# Digital.net
KiCad netlist of a schematic drawn in Altium Designer
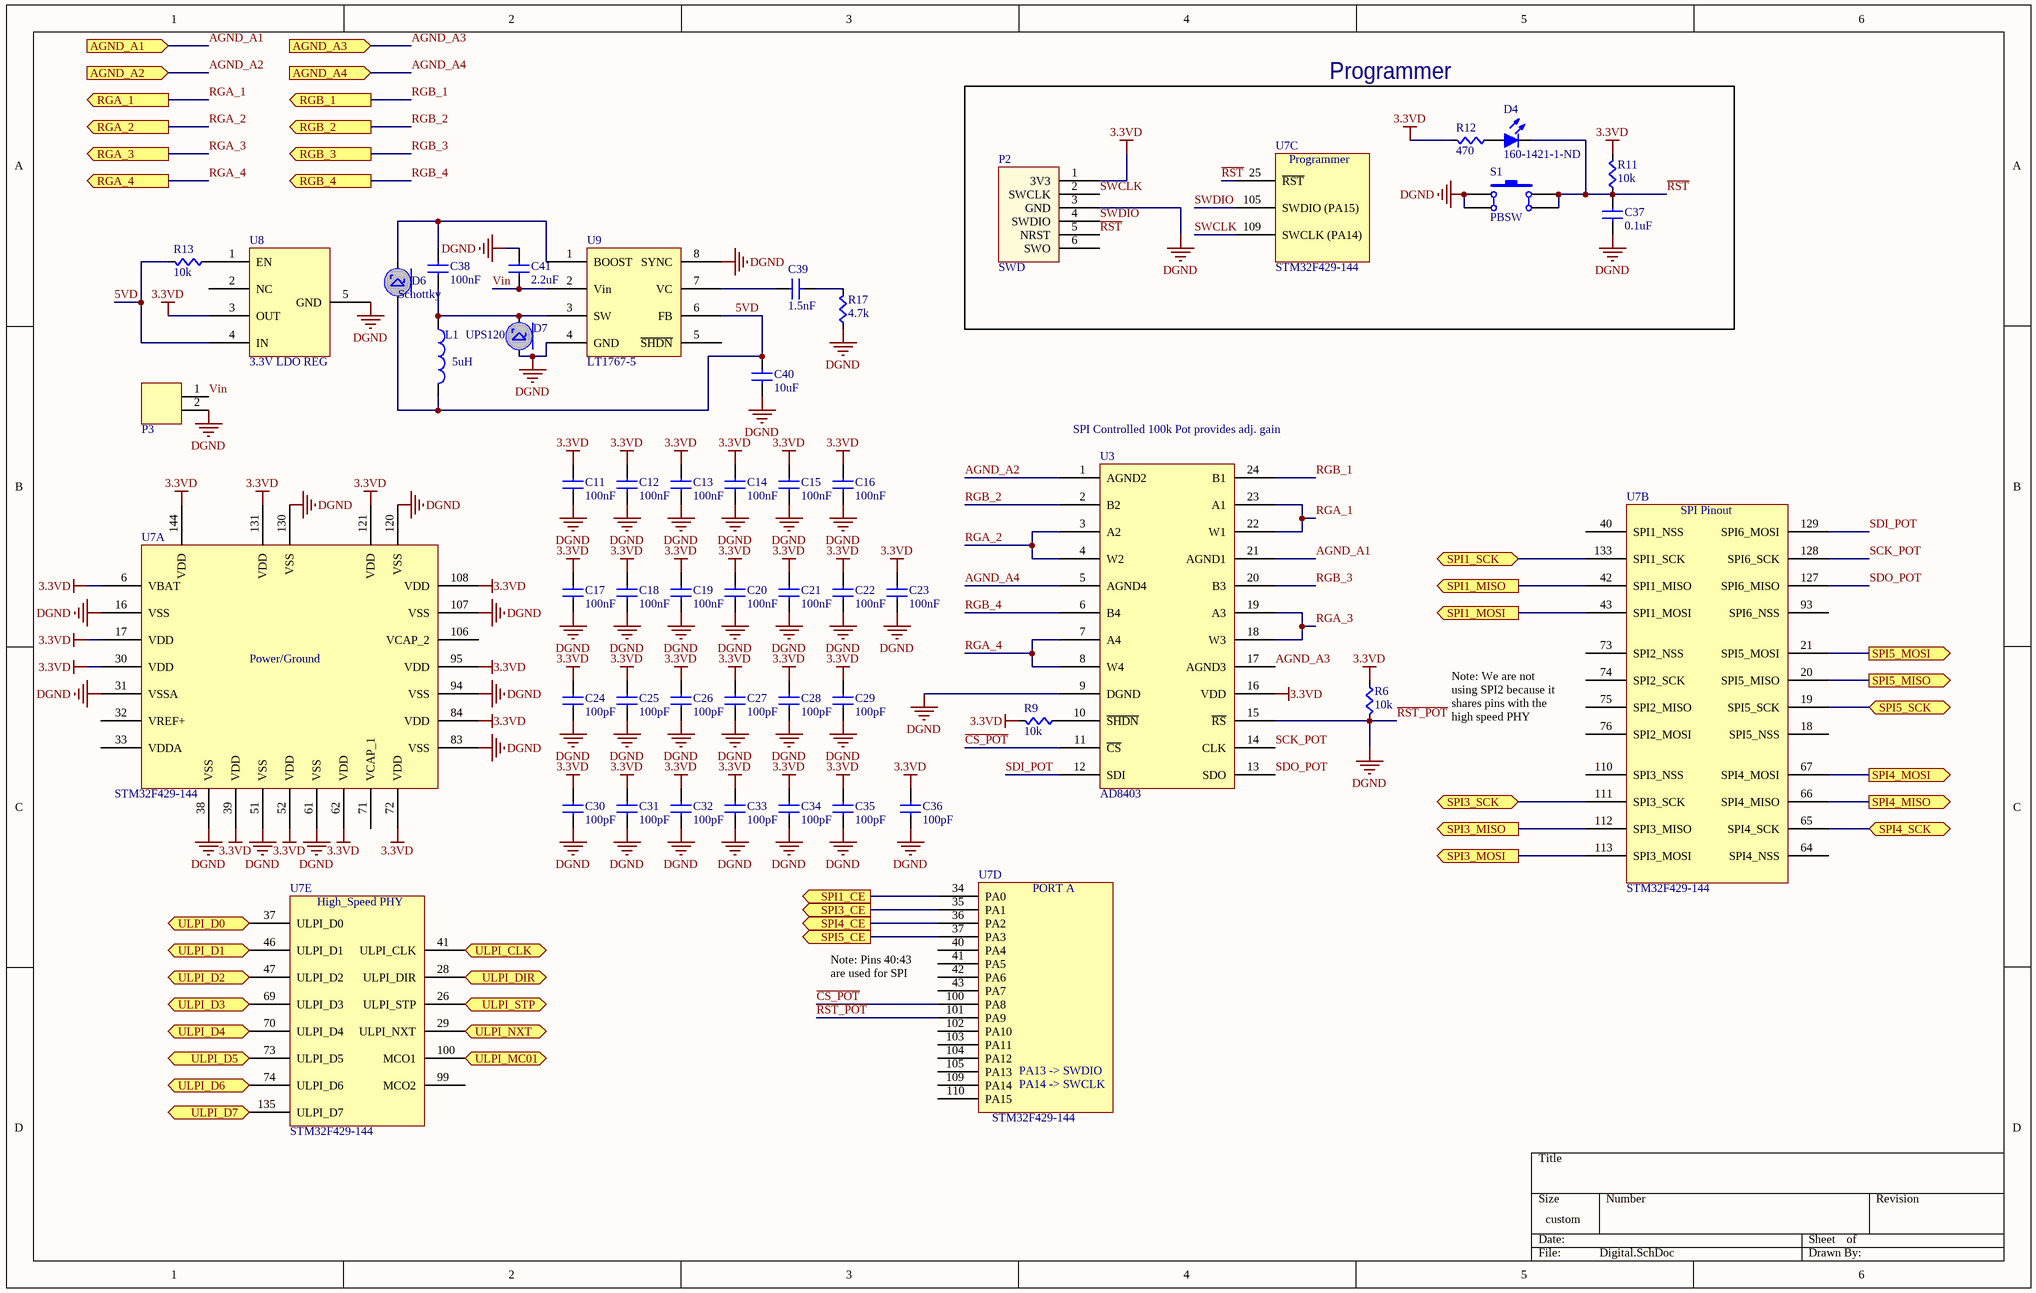
[diagram p0: Digital.SchDoc]

(export (version "E")
  (design (tool "Eeschema 10.0.6"))
  (components
    (comp (ref "C11")
      (value "100nF")
      (footprint "CAPC0603")
      (fields (field (name "Comment") "Cap"))
      (libsource (lib "SubjuGator8") (part "Cap"))
    )
    (comp (ref "C12")
      (value "100nF")
      (footprint "CAPC0603")
      (fields (field (name "Comment") "Cap"))
      (libsource (lib "SubjuGator8") (part "Cap"))
    )
    (comp (ref "C13")
      (value "100nF")
      (footprint "CAPC0603")
      (fields (field (name "Comment") "Cap"))
      (libsource (lib "SubjuGator8") (part "Cap"))
    )
    (comp (ref "C14")
      (value "100nF")
      (footprint "CAPC0603")
      (fields (field (name "Comment") "Cap"))
      (libsource (lib "SubjuGator8") (part "Cap"))
    )
    (comp (ref "C15")
      (value "100nF")
      (footprint "CAPC0603")
      (fields (field (name "Comment") "Cap"))
      (libsource (lib "SubjuGator8") (part "Cap"))
    )
    (comp (ref "C16")
      (value "100nF")
      (footprint "CAPC0603")
      (fields (field (name "Comment") "Cap"))
      (libsource (lib "SubjuGator8") (part "Cap"))
    )
    (comp (ref "C17")
      (value "100nF")
      (footprint "CAPC0603")
      (fields (field (name "Comment") "Cap"))
      (libsource (lib "SubjuGator8") (part "Cap"))
    )
    (comp (ref "C18")
      (value "100nF")
      (footprint "CAPC0603")
      (fields (field (name "Comment") "Cap"))
      (libsource (lib "SubjuGator8") (part "Cap"))
    )
    (comp (ref "C19")
      (value "100nF")
      (footprint "CAPC0603")
      (fields (field (name "Comment") "Cap"))
      (libsource (lib "SubjuGator8") (part "Cap"))
    )
    (comp (ref "C20")
      (value "100nF")
      (footprint "CAPC0603")
      (fields (field (name "Comment") "Cap"))
      (libsource (lib "SubjuGator8") (part "Cap"))
    )
    (comp (ref "C21")
      (value "100nF")
      (footprint "CAPC0603")
      (fields (field (name "Comment") "Cap"))
      (libsource (lib "SubjuGator8") (part "Cap"))
    )
    (comp (ref "C22")
      (value "100nF")
      (footprint "CAPC0603")
      (fields (field (name "Comment") "Cap"))
      (libsource (lib "SubjuGator8") (part "Cap"))
    )
    (comp (ref "C23")
      (value "100nF")
      (footprint "CAPC0603")
      (fields (field (name "Comment") "Cap"))
      (libsource (lib "SubjuGator8") (part "Cap"))
    )
    (comp (ref "C24")
      (value "100pF")
      (footprint "CAPC0603")
      (fields (field (name "Comment") "Cap"))
      (libsource (lib "SubjuGator8") (part "Cap"))
    )
    (comp (ref "C25")
      (value "100pF")
      (footprint "CAPC0603")
      (fields (field (name "Comment") "Cap"))
      (libsource (lib "SubjuGator8") (part "Cap"))
    )
    (comp (ref "C26")
      (value "100pF")
      (footprint "CAPC0603")
      (fields (field (name "Comment") "Cap"))
      (libsource (lib "SubjuGator8") (part "Cap"))
    )
    (comp (ref "C27")
      (value "100pF")
      (footprint "CAPC0603")
      (fields (field (name "Comment") "Cap"))
      (libsource (lib "SubjuGator8") (part "Cap"))
    )
    (comp (ref "C28")
      (value "100pF")
      (footprint "CAPC0603")
      (fields (field (name "Comment") "Cap"))
      (libsource (lib "SubjuGator8") (part "Cap"))
    )
    (comp (ref "C29")
      (value "100pF")
      (footprint "CAPC0603")
      (fields (field (name "Comment") "Cap"))
      (libsource (lib "SubjuGator8") (part "Cap"))
    )
    (comp (ref "C30")
      (value "100pF")
      (footprint "CAPC0603")
      (fields (field (name "Comment") "Cap"))
      (libsource (lib "SubjuGator8") (part "Cap"))
    )
    (comp (ref "C31")
      (value "100pF")
      (footprint "CAPC0603")
      (fields (field (name "Comment") "Cap"))
      (libsource (lib "SubjuGator8") (part "Cap"))
    )
    (comp (ref "C32")
      (value "100pF")
      (footprint "CAPC0603")
      (fields (field (name "Comment") "Cap"))
      (libsource (lib "SubjuGator8") (part "Cap"))
    )
    (comp (ref "C33")
      (value "100pF")
      (footprint "CAPC0603")
      (fields (field (name "Comment") "Cap"))
      (libsource (lib "SubjuGator8") (part "Cap"))
    )
    (comp (ref "C34")
      (value "100pF")
      (footprint "CAPC0603")
      (fields (field (name "Comment") "Cap"))
      (libsource (lib "SubjuGator8") (part "Cap"))
    )
    (comp (ref "C35")
      (value "100pF")
      (footprint "CAPC0603")
      (fields (field (name "Comment") "Cap"))
      (libsource (lib "SubjuGator8") (part "Cap"))
    )
    (comp (ref "C36")
      (value "100pF")
      (footprint "CAPC0603")
      (fields (field (name "Comment") "Cap"))
      (libsource (lib "SubjuGator8") (part "Cap"))
    )
    (comp (ref "C37")
      (value "0.1uF")
      (footprint "CAPC0603")
      (fields (field (name "Comment") "Cap"))
      (libsource (lib "SubjuGator8") (part "Cap"))
    )
    (comp (ref "C38")
      (value "100nF")
      (footprint "CAPC0603")
      (fields (field (name "Comment") "Cap"))
      (libsource (lib "SubjuGator8") (part "Cap"))
    )
    (comp (ref "C39")
      (value "1.5nF")
      (footprint "CAPC0603")
      (fields (field (name "Comment") "Cap"))
      (libsource (lib "SubjuGator8") (part "Cap"))
    )
    (comp (ref "C40")
      (value "10uF")
      (footprint "CAPC0603")
      (fields (field (name "Comment") "Cap"))
      (libsource (lib "SubjuGator8") (part "Cap"))
    )
    (comp (ref "C41")
      (value "2.2uF")
      (footprint "CAPC0603")
      (fields (field (name "Comment") "Cap"))
      (libsource (lib "SubjuGator8") (part "Cap"))
    )
    (comp (ref "D4")
      (value "LED-RED")
      (footprint "Hydrophone:LED0805-RED")
      (description "Light Emitting Diode - RED")
      (fields
        (field (name "MANUFACTURER PART NUMBER") "LTST-C171CKT")
        (field (name "MANUFACTURER") "Lite-On Inc")
        (field (name "SUPPLIER PART NUMBER") "160-1421-1-ND")
      )
      (libsource (lib "Hydrophone") (part "LED-RED"))
    )
    (comp (ref "D6")
      (value "Schottky")
      (footprint "SOD-323F")
      (description "DIODE SCHOTTKY 30V 100MA SOD323")
      (libsource (lib "Semiconductors") (part "CMDSH-3"))
    )
    (comp (ref "D7")
      (value "UPS120")
      (footprint "DO-216AA")
      (description "DIODE SCHOTTKY 20V 1A POWERMITE1")
      (libsource (lib "SubjuGator8") (part "UPS120"))
    )
    (comp (ref "L1")
      (value "5uH")
      (footprint "IND_2")
      (description "FIXED IND 5UH 4.7A 22 MOHM SMD")
      (libsource (lib "Passives") (part "SRR1206-5R0ML"))
    )
    (comp (ref "P2")
      (value "SWD")
      (footprint "SWD_STM32")
      (description "SWD connector matching the pinout on STM Discovery Boards")
      (libsource (lib "SubjuGator8") (part "SWD_STM32"))
    )
    (comp (ref "P3")
      (value "2-pin Horz Sherlock")
      (footprint "MOLEX-HDR-1X2-SHERLOCK-HORZ")
      (fields
        (field (name "MANUFACTURER PART NUMBER") "0353630260")
        (field (name "MANUFACTURER") "Molex Inc")
      )
      (libsource (lib "SubjuGator8") (part "MOLEX-HDR-1x2-SHERLOCK_RA"))
    )
    (comp (ref "R6")
      (value "10k")
      (footprint "RES0603")
      (fields (field (name "Comment") "Res"))
      (libsource (lib "SubjuGator8") (part "Res"))
    )
    (comp (ref "R9")
      (value "10k")
      (footprint "RES0603")
      (fields (field (name "Comment") "Res"))
      (libsource (lib "SubjuGator8") (part "Res"))
    )
    (comp (ref "R11")
      (value "10k")
      (footprint "RES0603")
      (fields (field (name "Comment") "Res"))
      (libsource (lib "Passives") (part "Res"))
    )
    (comp (ref "R12")
      (value "470")
      (footprint "RES0603")
      (fields (field (name "Comment") "Res"))
      (libsource (lib "SubjuGator8") (part "Res"))
    )
    (comp (ref "R13")
      (value "10k")
      (footprint "RES0603")
      (fields (field (name "Comment") "Res"))
      (libsource (lib "SubjuGator8") (part "Res"))
    )
    (comp (ref "R17")
      (value "4.7k")
      (footprint "RES0603")
      (fields (field (name "Comment") "Res"))
      (libsource (lib "SubjuGator8") (part "Res"))
    )
    (comp (ref "S1")
      (value "PBSW")
      (footprint "Hydrophone:PBSW")
      (description "Push Button Switch")
      (fields
        (field (name "MANUFACTURER") "Panasonic Electronic Components")
        (field (name "MANUFACTURER PART NUMBER") "EVQ-9P105M")
        (field (name "PUBLISHER") "Altium Limited")
      )
      (libsource (lib "Hydrophone") (part "SW-PB"))
    )
    (comp (ref "U3")
      (value "AD8403")
      (footprint "SOIC-24n")
      (description "IC POT DGTL 8BIT 100K 4CH 24SOIC")
      (libsource (lib "SubjuGator8") (part "AD8403"))
    )
    (comp (ref "U7")
      (value "STM32F429-144")
      (footprint "LQFP-144")
      (description "IC MCU ARM 2MB FLASH 144LQFP")
      (libsource (lib "SubjuGator8") (part "STM32F429-144"))
    )
    (comp (ref "U8")
      (value "3.3V LDO REG")
      (footprint "SOT223-8N")
      (description "IC REG LDO 3.3V 0.5A SOT223-5")
      (libsource (lib "SubjuGator8") (part "LP38691"))
    )
    (comp (ref "U9")
      (value "LT1767-5")
      (footprint "MSOP-8n")
      (description "IC REG BUCK 5V 1.5A 8MSOP")
      (libsource (lib "SubjuGator8") (part "LT1767-5"))
    )
  )
  (nets
    (net (code "1") (name "/5VD") (class "Default")
      (node (ref "C40") (pin "1") (pinfunction "A_1") (pintype "passive"))
      (node (ref "D6") (pin "A") (pinfunction "A_A") (pintype "passive"))
      (node (ref "L1") (pin "2") (pinfunction "B_2") (pintype "passive"))
      (node (ref "R13") (pin "1") (pinfunction "A_1") (pintype "passive"))
      (node (ref "U8") (pin "4") (pinfunction "IN_4") (pintype "passive"))
      (node (ref "U9") (pin "6") (pinfunction "FB_6") (pintype "passive"))
    )
    (net (code "2") (name "/AGND_A1") (class "Default")
      (node (ref "U3") (pin "21") (pinfunction "AGND1_21") (pintype "passive"))
    )
    (net (code "3") (name "/AGND_A2") (class "Default")
      (node (ref "U3") (pin "1") (pinfunction "AGND2_1") (pintype "passive"))
    )
    (net (code "4") (name "/AGND_A3") (class "Default")
      (node (ref "U3") (pin "17") (pinfunction "AGND3_17") (pintype "passive"))
    )
    (net (code "5") (name "/AGND_A4") (class "Default")
      (node (ref "U3") (pin "5") (pinfunction "AGND4_5") (pintype "passive"))
    )
    (net (code "6") (name "/RGA_1") (class "Default")
      (node (ref "U3") (pin "22") (pinfunction "W1_22") (pintype "passive"))
      (node (ref "U3") (pin "23") (pinfunction "A1_23") (pintype "passive"))
    )
    (net (code "7") (name "/RGA_2") (class "Default")
      (node (ref "U3") (pin "3") (pinfunction "A2_3") (pintype "passive"))
      (node (ref "U3") (pin "4") (pinfunction "W2_4") (pintype "passive"))
    )
    (net (code "8") (name "/RGA_3") (class "Default")
      (node (ref "U3") (pin "18") (pinfunction "W3_18") (pintype "passive"))
      (node (ref "U3") (pin "19") (pinfunction "A3_19") (pintype "passive"))
    )
    (net (code "9") (name "/RGA_4") (class "Default")
      (node (ref "U3") (pin "7") (pinfunction "A4_7") (pintype "passive"))
      (node (ref "U3") (pin "8") (pinfunction "W4_8") (pintype "passive"))
    )
    (net (code "10") (name "/RGB_1") (class "Default")
      (node (ref "U3") (pin "24") (pinfunction "B1_24") (pintype "passive"))
    )
    (net (code "11") (name "/RGB_2") (class "Default")
      (node (ref "U3") (pin "2") (pinfunction "B2_2") (pintype "passive"))
    )
    (net (code "12") (name "/RGB_3") (class "Default")
      (node (ref "U3") (pin "20") (pinfunction "B3_20") (pintype "passive"))
    )
    (net (code "13") (name "/RGB_4") (class "Default")
      (node (ref "U3") (pin "6") (pinfunction "B4_6") (pintype "passive"))
    )
    (net (code "14") (name "/SCK_POT") (class "Default")
      (node (ref "U3") (pin "14") (pinfunction "CLK_14") (pintype "passive"))
      (node (ref "U7") (pin "128") (pinfunction "SPI6_SCK_128") (pintype "passive"))
    )
    (net (code "15") (name "/SDI_POT") (class "Default")
      (node (ref "U3") (pin "12") (pinfunction "SDI_12") (pintype "passive"))
      (node (ref "U7") (pin "129") (pinfunction "SPI6_MOSI_129") (pintype "passive"))
    )
    (net (code "16") (name "/SDO_POT") (class "Default")
      (node (ref "U3") (pin "13") (pinfunction "SDO_13") (pintype "passive"))
      (node (ref "U7") (pin "127") (pinfunction "SPI6_MISO_127") (pintype "passive"))
    )
    (net (code "17") (name "/SPI1_CE") (class "Default")
      (node (ref "U7") (pin "34") (pinfunction "PA0_34") (pintype "passive"))
    )
    (net (code "18") (name "/SPI1_MISO") (class "Default")
      (node (ref "U7") (pin "42") (pinfunction "SPI1_MISO_42") (pintype "passive"))
    )
    (net (code "19") (name "/SPI1_MOSI") (class "Default")
      (node (ref "U7") (pin "43") (pinfunction "SPI1_MOSI_43") (pintype "passive"))
    )
    (net (code "20") (name "/SPI1_SCK") (class "Default")
      (node (ref "U7") (pin "133") (pinfunction "SPI1_SCK_133") (pintype "passive"))
    )
    (net (code "21") (name "/SPI3_CE") (class "Default")
      (node (ref "U7") (pin "35") (pinfunction "PA1_35") (pintype "passive"))
    )
    (net (code "22") (name "/SPI3_MISO") (class "Default")
      (node (ref "U7") (pin "112") (pinfunction "SPI3_MISO_112") (pintype "passive"))
    )
    (net (code "23") (name "/SPI3_MOSI") (class "Default")
      (node (ref "U7") (pin "113") (pinfunction "SPI3_MOSI_113") (pintype "passive"))
    )
    (net (code "24") (name "/SPI3_SCK") (class "Default")
      (node (ref "U7") (pin "111") (pinfunction "SPI3_SCK_111") (pintype "passive"))
    )
    (net (code "25") (name "/SPI4_CE") (class "Default")
      (node (ref "U7") (pin "36") (pinfunction "PA2_36") (pintype "passive"))
    )
    (net (code "26") (name "/SPI4_MISO") (class "Default")
      (node (ref "U7") (pin "66") (pinfunction "SPI4_MISO_66") (pintype "passive"))
    )
    (net (code "27") (name "/SPI4_MOSI") (class "Default")
      (node (ref "U7") (pin "67") (pinfunction "SPI4_MOSI_67") (pintype "passive"))
    )
    (net (code "28") (name "/SPI4_SCK") (class "Default")
      (node (ref "U7") (pin "65") (pinfunction "SPI4_SCK_65") (pintype "passive"))
    )
    (net (code "29") (name "/SPI5_CE") (class "Default")
      (node (ref "U7") (pin "37") (pinfunction "PA3_37") (pintype "passive"))
    )
    (net (code "30") (name "/SPI5_MISO") (class "Default")
      (node (ref "U7") (pin "20") (pinfunction "SPI5_MISO_20") (pintype "passive"))
    )
    (net (code "31") (name "/SPI5_MOSI") (class "Default")
      (node (ref "U7") (pin "21") (pinfunction "SPI5_MOSI_21") (pintype "passive"))
    )
    (net (code "32") (name "/SPI5_SCK") (class "Default")
      (node (ref "U7") (pin "19") (pinfunction "SPI5_SCK_19") (pintype "passive"))
    )
    (net (code "33") (name "/SWCLK") (class "Default")
      (node (ref "P2") (pin "2") (pinfunction "SWCLK_2") (pintype "passive"))
      (node (ref "U7") (pin "109") (pinfunction "SWCLK_(PA14)_109") (pintype "passive"))
    )
    (net (code "34") (name "/SWDIO") (class "Default")
      (node (ref "P2") (pin "4") (pinfunction "SWDIO_4") (pintype "passive"))
      (node (ref "U7") (pin "105") (pinfunction "SWDIO_(PA15)_105") (pintype "passive"))
    )
    (net (code "36") (name "/ULPI_CLK") (class "Default")
      (node (ref "U7") (pin "41") (pinfunction "ULPI_CLK_41") (pintype "passive"))
    )
    (net (code "37") (name "/ULPI_D0") (class "Default")
      (node (ref "U7") (pin "37") (pinfunction "ULPI_D0_37") (pintype "passive"))
    )
    (net (code "38") (name "/ULPI_D1") (class "Default")
      (node (ref "U7") (pin "46") (pinfunction "ULPI_D1_46") (pintype "passive"))
    )
    (net (code "39") (name "/ULPI_D2") (class "Default")
      (node (ref "U7") (pin "47") (pinfunction "ULPI_D2_47") (pintype "passive"))
    )
    (net (code "40") (name "/ULPI_D3") (class "Default")
      (node (ref "U7") (pin "69") (pinfunction "ULPI_D3_69") (pintype "passive"))
    )
    (net (code "41") (name "/ULPI_D4") (class "Default")
      (node (ref "U7") (pin "70") (pinfunction "ULPI_D4_70") (pintype "passive"))
    )
    (net (code "42") (name "/ULPI_D5") (class "Default")
      (node (ref "U7") (pin "73") (pinfunction "ULPI_D5_73") (pintype "passive"))
    )
    (net (code "43") (name "/ULPI_D6") (class "Default")
      (node (ref "U7") (pin "74") (pinfunction "ULPI_D6_74") (pintype "passive"))
    )
    (net (code "48") (name "/ULPI_D7") (class "Default")
      (node (ref "U7") (pin "135") (pinfunction "ULPI_D7_135") (pintype "passive"))
    )
    (net (code "49") (name "/ULPI_DIR") (class "Default")
      (node (ref "U7") (pin "28") (pinfunction "ULPI_DIR_28") (pintype "passive"))
    )
    (net (code "50") (name "/ULPI_MC01") (class "Default")
      (node (ref "U7") (pin "100") (pinfunction "MCO1_100") (pintype "passive"))
    )
    (net (code "51") (name "/ULPI_NXT") (class "Default")
      (node (ref "U7") (pin "29") (pinfunction "ULPI_NXT_29") (pintype "passive"))
    )
    (net (code "52") (name "/ULPI_STP") (class "Default")
      (node (ref "U7") (pin "26") (pinfunction "ULPI_STP_26") (pintype "passive"))
    )
    (net (code "53") (name "/Vin") (class "Default")
      (node (ref "C41") (pin "1") (pinfunction "A_1") (pintype "passive"))
      (node (ref "P3") (pin "1") (pinfunction "1_1") (pintype "passive"))
      (node (ref "U9") (pin "2") (pinfunction "Vin_2") (pintype "passive"))
    )
    (net (code "54") (name "/~{CS_POT}") (class "Default")
      (node (ref "U3") (pin "11") (pinfunction "~{CS}_11") (pintype "passive"))
      (node (ref "U7") (pin "100") (pinfunction "PA8_100") (pintype "passive"))
    )
    (net (code "55") (name "/~{RST}") (class "Default")
      (node (ref "C37") (pin "1") (pinfunction "A_1") (pintype "passive"))
      (node (ref "D4") (pin "1") (pinfunction "K_1") (pintype "passive"))
      (node (ref "P2") (pin "5") (pinfunction "NRST_5") (pintype "passive"))
      (node (ref "R11") (pin "2") (pinfunction "B_2") (pintype "passive"))
      (node (ref "S1") (pin "3") (pinfunction "B_3") (pintype "passive"))
      (node (ref "S1") (pin "4") (pinfunction "B'_4") (pintype "passive"))
      (node (ref "U7") (pin "25") (pinfunction "~{RST}_25") (pintype "passive"))
    )
    (net (code "56") (name "3.3VD") (class "Default")
      (node (ref "C11") (pin "1") (pinfunction "A_1") (pintype "passive"))
      (node (ref "C12") (pin "1") (pinfunction "A_1") (pintype "passive"))
      (node (ref "C13") (pin "1") (pinfunction "A_1") (pintype "passive"))
      (node (ref "C14") (pin "1") (pinfunction "A_1") (pintype "passive"))
      (node (ref "C15") (pin "1") (pinfunction "A_1") (pintype "passive"))
      (node (ref "C16") (pin "1") (pinfunction "A_1") (pintype "passive"))
      (node (ref "C17") (pin "1") (pinfunction "A_1") (pintype "passive"))
      (node (ref "C18") (pin "1") (pinfunction "A_1") (pintype "passive"))
      (node (ref "C19") (pin "1") (pinfunction "A_1") (pintype "passive"))
      (node (ref "C20") (pin "1") (pinfunction "A_1") (pintype "passive"))
      (node (ref "C21") (pin "1") (pinfunction "A_1") (pintype "passive"))
      (node (ref "C22") (pin "1") (pinfunction "A_1") (pintype "passive"))
      (node (ref "C23") (pin "1") (pinfunction "A_1") (pintype "passive"))
      (node (ref "C24") (pin "1") (pinfunction "A_1") (pintype "passive"))
      (node (ref "C25") (pin "1") (pinfunction "A_1") (pintype "passive"))
      (node (ref "C26") (pin "1") (pinfunction "A_1") (pintype "passive"))
      (node (ref "C27") (pin "1") (pinfunction "A_1") (pintype "passive"))
      (node (ref "C28") (pin "1") (pinfunction "A_1") (pintype "passive"))
      (node (ref "C29") (pin "1") (pinfunction "A_1") (pintype "passive"))
      (node (ref "C30") (pin "1") (pinfunction "A_1") (pintype "passive"))
      (node (ref "C31") (pin "1") (pinfunction "A_1") (pintype "passive"))
      (node (ref "C32") (pin "1") (pinfunction "A_1") (pintype "passive"))
      (node (ref "C33") (pin "1") (pinfunction "A_1") (pintype "passive"))
      (node (ref "C34") (pin "1") (pinfunction "A_1") (pintype "passive"))
      (node (ref "C35") (pin "1") (pinfunction "A_1") (pintype "passive"))
      (node (ref "C36") (pin "1") (pinfunction "A_1") (pintype "passive"))
      (node (ref "P2") (pin "1") (pinfunction "3V3_1") (pintype "passive"))
      (node (ref "R11") (pin "1") (pinfunction "A_1") (pintype "passive"))
      (node (ref "R12") (pin "1") (pinfunction "A_1") (pintype "passive"))
      (node (ref "R6") (pin "2") (pinfunction "B_2") (pintype "passive"))
      (node (ref "R9") (pin "1") (pinfunction "A_1") (pintype "passive"))
      (node (ref "U3") (pin "16") (pinfunction "VDD_16") (pintype "passive"))
      (node (ref "U7") (pin "108") (pinfunction "VDD_108") (pintype "passive"))
      (node (ref "U7") (pin "121") (pinfunction "VDD_121") (pintype "passive"))
      (node (ref "U7") (pin "131") (pinfunction "VDD_131") (pintype "passive"))
      (node (ref "U7") (pin "144") (pinfunction "VDD_144") (pintype "passive"))
      (node (ref "U7") (pin "17") (pinfunction "VDD_17") (pintype "passive"))
      (node (ref "U7") (pin "30") (pinfunction "VDD_30") (pintype "passive"))
      (node (ref "U7") (pin "39") (pinfunction "VDD_39") (pintype "passive"))
      (node (ref "U7") (pin "52") (pinfunction "VDD_52") (pintype "passive"))
      (node (ref "U7") (pin "6") (pinfunction "VBAT_6") (pintype "passive"))
      (node (ref "U7") (pin "62") (pinfunction "VDD_62") (pintype "passive"))
      (node (ref "U7") (pin "72") (pinfunction "VDD_72") (pintype "passive"))
      (node (ref "U7") (pin "84") (pinfunction "VDD_84") (pintype "passive"))
      (node (ref "U7") (pin "95") (pinfunction "VDD_95") (pintype "passive"))
      (node (ref "U8") (pin "3") (pinfunction "OUT_3") (pintype "passive"))
    )
    (net (code "57") (name "DGND") (class "Default")
      (node (ref "C11") (pin "2") (pinfunction "B_2") (pintype "passive"))
      (node (ref "C12") (pin "2") (pinfunction "B_2") (pintype "passive"))
      (node (ref "C13") (pin "2") (pinfunction "B_2") (pintype "passive"))
      (node (ref "C14") (pin "2") (pinfunction "B_2") (pintype "passive"))
      (node (ref "C15") (pin "2") (pinfunction "B_2") (pintype "passive"))
      (node (ref "C16") (pin "2") (pinfunction "B_2") (pintype "passive"))
      (node (ref "C17") (pin "2") (pinfunction "B_2") (pintype "passive"))
      (node (ref "C18") (pin "2") (pinfunction "B_2") (pintype "passive"))
      (node (ref "C19") (pin "2") (pinfunction "B_2") (pintype "passive"))
      (node (ref "C20") (pin "2") (pinfunction "B_2") (pintype "passive"))
      (node (ref "C21") (pin "2") (pinfunction "B_2") (pintype "passive"))
      (node (ref "C22") (pin "2") (pinfunction "B_2") (pintype "passive"))
      (node (ref "C23") (pin "2") (pinfunction "B_2") (pintype "passive"))
      (node (ref "C24") (pin "2") (pinfunction "B_2") (pintype "passive"))
      (node (ref "C25") (pin "2") (pinfunction "B_2") (pintype "passive"))
      (node (ref "C26") (pin "2") (pinfunction "B_2") (pintype "passive"))
      (node (ref "C27") (pin "2") (pinfunction "B_2") (pintype "passive"))
      (node (ref "C28") (pin "2") (pinfunction "B_2") (pintype "passive"))
      (node (ref "C29") (pin "2") (pinfunction "B_2") (pintype "passive"))
      (node (ref "C30") (pin "2") (pinfunction "B_2") (pintype "passive"))
      (node (ref "C31") (pin "2") (pinfunction "B_2") (pintype "passive"))
      (node (ref "C32") (pin "2") (pinfunction "B_2") (pintype "passive"))
      (node (ref "C33") (pin "2") (pinfunction "B_2") (pintype "passive"))
      (node (ref "C34") (pin "2") (pinfunction "B_2") (pintype "passive"))
      (node (ref "C35") (pin "2") (pinfunction "B_2") (pintype "passive"))
      (node (ref "C36") (pin "2") (pinfunction "B_2") (pintype "passive"))
      (node (ref "C37") (pin "2") (pinfunction "B_2") (pintype "passive"))
      (node (ref "C40") (pin "2") (pinfunction "B_2") (pintype "passive"))
      (node (ref "C41") (pin "2") (pinfunction "B_2") (pintype "passive"))
      (node (ref "D7") (pin "A") (pinfunction "A_A") (pintype "passive"))
      (node (ref "P2") (pin "3") (pinfunction "GND_3") (pintype "passive"))
      (node (ref "P3") (pin "2") (pinfunction "2_2") (pintype "passive"))
      (node (ref "R17") (pin "2") (pinfunction "B_2") (pintype "passive"))
      (node (ref "R6") (pin "1") (pinfunction "A_1") (pintype "passive"))
      (node (ref "S1") (pin "1") (pinfunction "A_1") (pintype "passive"))
      (node (ref "S1") (pin "2") (pinfunction "A'_2") (pintype "passive"))
      (node (ref "U3") (pin "15") (pinfunction "~{RS}_15") (pintype "passive"))
      (node (ref "U3") (pin "9") (pinfunction "DGND_9") (pintype "passive"))
      (node (ref "U7") (pin "101") (pinfunction "PA9_101") (pintype "passive"))
      (node (ref "U7") (pin "107") (pinfunction "VSS_107") (pintype "passive"))
      (node (ref "U7") (pin "120") (pinfunction "VSS_120") (pintype "passive"))
      (node (ref "U7") (pin "130") (pinfunction "VSS_130") (pintype "passive"))
      (node (ref "U7") (pin "16") (pinfunction "VSS_16") (pintype "passive"))
      (node (ref "U7") (pin "31") (pinfunction "VSSA_31") (pintype "passive"))
      (node (ref "U7") (pin "38") (pinfunction "VSS_38") (pintype "passive"))
      (node (ref "U7") (pin "51") (pinfunction "VSS_51") (pintype "passive"))
      (node (ref "U7") (pin "61") (pinfunction "VSS_61") (pintype "passive"))
      (node (ref "U7") (pin "83") (pinfunction "VSS_83") (pintype "passive"))
      (node (ref "U7") (pin "94") (pinfunction "VSS_94") (pintype "passive"))
      (node (ref "U8") (pin "5") (pinfunction "GND_5") (pintype "passive"))
      (node (ref "U9") (pin "4") (pinfunction "GND_4") (pintype "passive"))
      (node (ref "U9") (pin "8") (pinfunction "SYNC_8") (pintype "passive"))
    )
    (net (code "58") (name "Net-(C38-A)") (class "Default")
      (node (ref "C38") (pin "1") (pinfunction "A_1") (pintype "passive"))
      (node (ref "D6") (pin "C") (pinfunction "C_C") (pintype "passive"))
      (node (ref "U9") (pin "1") (pinfunction "BOOST_1") (pintype "passive"))
    )
    (net (code "59") (name "Net-(C38-B)") (class "Default")
      (node (ref "C38") (pin "2") (pinfunction "B_2") (pintype "passive"))
      (node (ref "D7") (pin "C") (pinfunction "C_C") (pintype "passive"))
      (node (ref "L1") (pin "1") (pinfunction "A_1") (pintype "passive"))
      (node (ref "U9") (pin "3") (pinfunction "SW_3") (pintype "passive"))
    )
    (net (code "60") (name "Net-(C39-A)") (class "Default")
      (node (ref "C39") (pin "1") (pinfunction "A_1") (pintype "passive"))
      (node (ref "U9") (pin "7") (pinfunction "VC_7") (pintype "passive"))
    )
    (net (code "61") (name "Net-(C39-B)") (class "Default")
      (node (ref "C39") (pin "2") (pinfunction "B_2") (pintype "passive"))
      (node (ref "R17") (pin "1") (pinfunction "A_1") (pintype "passive"))
    )
    (net (code "62") (name "Net-(D4-A)") (class "Default")
      (node (ref "D4") (pin "2") (pinfunction "A_2") (pintype "passive"))
      (node (ref "R12") (pin "2") (pinfunction "B_2") (pintype "passive"))
    )
    (net (code "63") (name "Net-(R9-B)") (class "Default")
      (node (ref "R9") (pin "2") (pinfunction "B_2") (pintype "passive"))
      (node (ref "U3") (pin "10") (pinfunction "~{SHDN}_10") (pintype "passive"))
    )
    (net (code "64") (name "Net-(R13-B)") (class "Default")
      (node (ref "R13") (pin "2") (pinfunction "B_2") (pintype "passive"))
      (node (ref "U8") (pin "1") (pinfunction "EN_1") (pintype "passive"))
    )
    (net (code "65") (name "unconnected-(P2-SWO-Pad6)") (class "Default")
      (node (ref "P2") (pin "6") (pinfunction "SWO_6") (pintype "passive"))
    )
    (net (code "66") (name "unconnected-(U7A-VCAP_1-Pad71)") (class "Default")
      (node (ref "U7") (pin "71") (pinfunction "VCAP_1_71") (pintype "passive"))
    )
    (net (code "67") (name "unconnected-(U7A-VCAP_2-Pad106)") (class "Default")
      (node (ref "U7") (pin "106") (pinfunction "VCAP_2_106") (pintype "passive"))
    )
    (net (code "68") (name "unconnected-(U7A-VDDA-Pad33)") (class "Default")
      (node (ref "U7") (pin "33") (pinfunction "VDDA_33") (pintype "passive"))
    )
    (net (code "69") (name "unconnected-(U7A-VREF+-Pad32)") (class "Default")
      (node (ref "U7") (pin "32") (pinfunction "VREF+_32") (pintype "passive"))
    )
    (net (code "70") (name "unconnected-(U7B-SPI1_NSS-Pad40)") (class "Default")
      (node (ref "U7") (pin "40") (pinfunction "SPI1_NSS_40") (pintype "passive"))
    )
    (net (code "71") (name "unconnected-(U7B-SPI2_MISO-Pad75)") (class "Default")
      (node (ref "U7") (pin "75") (pinfunction "SPI2_MISO_75") (pintype "passive"))
    )
    (net (code "72") (name "unconnected-(U7B-SPI2_MOSI-Pad76)") (class "Default")
      (node (ref "U7") (pin "76") (pinfunction "SPI2_MOSI_76") (pintype "passive"))
    )
    (net (code "73") (name "unconnected-(U7B-SPI2_NSS-Pad73)") (class "Default")
      (node (ref "U7") (pin "73") (pinfunction "SPI2_NSS_73") (pintype "passive"))
    )
    (net (code "74") (name "unconnected-(U7B-SPI2_SCK-Pad74)") (class "Default")
      (node (ref "U7") (pin "74") (pinfunction "SPI2_SCK_74") (pintype "passive"))
    )
    (net (code "75") (name "unconnected-(U7B-SPI3_NSS-Pad110)") (class "Default")
      (node (ref "U7") (pin "110") (pinfunction "SPI3_NSS_110") (pintype "passive"))
    )
    (net (code "76") (name "unconnected-(U7B-SPI4_NSS-Pad64)") (class "Default")
      (node (ref "U7") (pin "64") (pinfunction "SPI4_NSS_64") (pintype "passive"))
    )
    (net (code "77") (name "unconnected-(U7B-SPI5_NSS-Pad18)") (class "Default")
      (node (ref "U7") (pin "18") (pinfunction "SPI5_NSS_18") (pintype "passive"))
    )
    (net (code "78") (name "unconnected-(U7B-SPI6_NSS-Pad93)") (class "Default")
      (node (ref "U7") (pin "93") (pinfunction "SPI6_NSS_93") (pintype "passive"))
    )
    (net (code "79") (name "unconnected-(U7D-PA4-Pad40)") (class "Default")
      (node (ref "U7") (pin "40") (pinfunction "PA4_40") (pintype "passive"))
    )
    (net (code "80") (name "unconnected-(U7D-PA5-Pad41)") (class "Default")
      (node (ref "U7") (pin "41") (pinfunction "PA5_41") (pintype "passive"))
    )
    (net (code "81") (name "unconnected-(U7D-PA6-Pad42)") (class "Default")
      (node (ref "U7") (pin "42") (pinfunction "PA6_42") (pintype "passive"))
    )
    (net (code "82") (name "unconnected-(U7D-PA7-Pad43)") (class "Default")
      (node (ref "U7") (pin "43") (pinfunction "PA7_43") (pintype "passive"))
    )
    (net (code "83") (name "unconnected-(U7D-PA10-Pad102)") (class "Default")
      (node (ref "U7") (pin "102") (pinfunction "PA10_102") (pintype "passive"))
    )
    (net (code "84") (name "unconnected-(U7D-PA11-Pad103)") (class "Default")
      (node (ref "U7") (pin "103") (pinfunction "PA11_103") (pintype "passive"))
    )
    (net (code "85") (name "unconnected-(U7D-PA12-Pad104)") (class "Default")
      (node (ref "U7") (pin "104") (pinfunction "PA12_104") (pintype "passive"))
    )
    (net (code "86") (name "unconnected-(U7D-PA13-Pad105)") (class "Default")
      (node (ref "U7") (pin "105") (pinfunction "PA13_105") (pintype "passive"))
    )
    (net (code "87") (name "unconnected-(U7D-PA14-Pad109)") (class "Default")
      (node (ref "U7") (pin "109") (pinfunction "PA14_109") (pintype "passive"))
    )
    (net (code "88") (name "unconnected-(U7D-PA15-Pad110)") (class "Default")
      (node (ref "U7") (pin "110") (pinfunction "PA15_110") (pintype "passive"))
    )
    (net (code "89") (name "unconnected-(U7E-MCO2-Pad99)") (class "Default")
      (node (ref "U7") (pin "99") (pinfunction "MCO2_99") (pintype "passive"))
    )
    (net (code "90") (name "unconnected-(U8-NC-Pad2)") (class "Default")
      (node (ref "U8") (pin "2") (pinfunction "NC_2") (pintype "passive"))
    )
    (net (code "91") (name "unconnected-(U9-~{SHDN}-Pad5)") (class "Default")
      (node (ref "U9") (pin "5") (pinfunction "~{SHDN}_5") (pintype "passive"))
    )
  )
)
